# galaxydriveV3_5.net
KiCad netlist of a schematic drawn in EAGLE
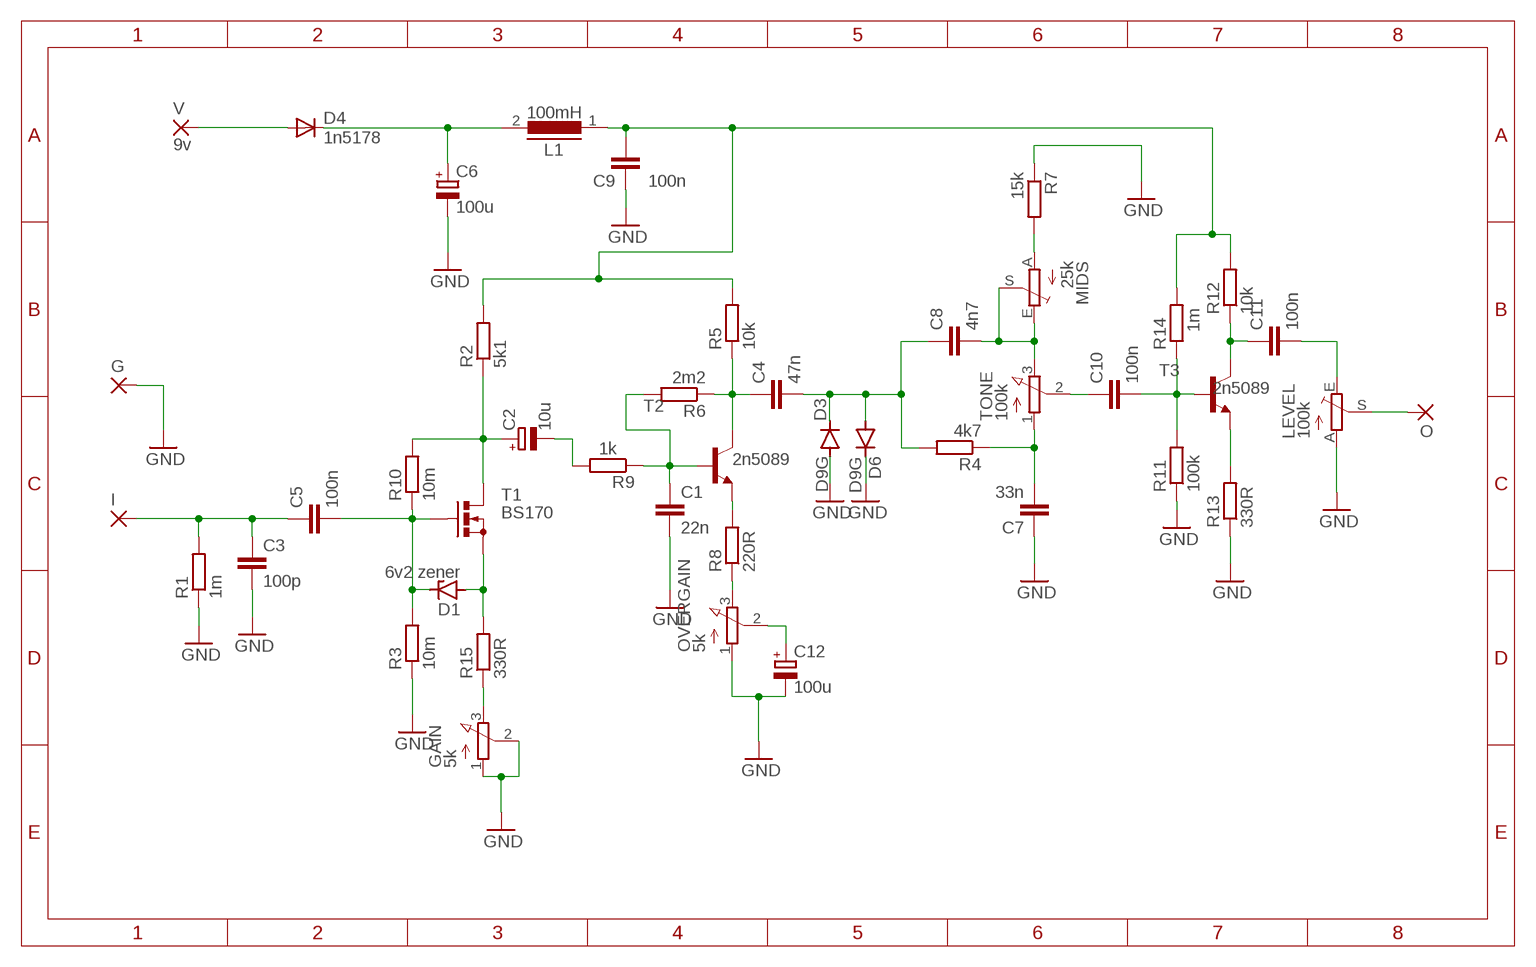
[diagram p0: schematic, sheet 1]

(export (version "E")
  (design (tool "Eeschema 10.0.6"))
  (components
    (comp (ref "C1")
      (value "22n")
      (footprint "eagle-import:C5B2.5")
      (libsource (lib "eagle-import") (part "C5/2.5"))
    )
    (comp (ref "C2")
      (value "10u")
      (footprint "eagle-import:E1,8-4")
      (libsource (lib "eagle-import") (part "CPOL-EUE1.8-4"))
    )
    (comp (ref "C3")
      (value "100p")
      (footprint "eagle-import:C5B2.5")
      (libsource (lib "eagle-import") (part "C5/2.5"))
    )
    (comp (ref "C4")
      (value "47n")
      (footprint "eagle-import:C5B2.5")
      (libsource (lib "eagle-import") (part "C5/2.5"))
    )
    (comp (ref "C5")
      (value "100n")
      (footprint "eagle-import:C5B2.5")
      (libsource (lib "eagle-import") (part "C5/2.5"))
    )
    (comp (ref "C6")
      (value "100u")
      (footprint "eagle-import:E2-4")
      (libsource (lib "eagle-import") (part "CPOL-EUE2-4"))
    )
    (comp (ref "C7")
      (value "33n")
      (footprint "eagle-import:C5B2.5")
      (libsource (lib "eagle-import") (part "C5/2.5"))
    )
    (comp (ref "C8")
      (value "4n7")
      (footprint "eagle-import:C5B2.5")
      (libsource (lib "eagle-import") (part "C5/2.5"))
    )
    (comp (ref "C9")
      (value "100n")
      (footprint "eagle-import:C5B2.5")
      (libsource (lib "eagle-import") (part "C5/2.5"))
    )
    (comp (ref "C10")
      (value "100n")
      (footprint "eagle-import:C5B2.5")
      (libsource (lib "eagle-import") (part "C5/2.5"))
    )
    (comp (ref "C11")
      (value "100n")
      (footprint "eagle-import:C5B2.5")
      (libsource (lib "eagle-import") (part "C5/2.5"))
    )
    (comp (ref "C12")
      (value "100u")
      (footprint "eagle-import:E2-4")
      (libsource (lib "eagle-import") (part "CPOL-EUE2-4"))
    )
    (comp (ref "D1")
      (value "6v2 zener")
      (footprint "eagle-import:DO34Z7")
      (libsource (lib "eagle-import") (part "BZX90"))
    )
    (comp (ref "D3")
      (value "D9G")
      (footprint "eagle-import:DO07")
      (libsource (lib "eagle-import") (part "OA91"))
    )
    (comp (ref "D4")
      (value "1n5178")
      (footprint "eagle-import:D-7.5")
      (libsource (lib "eagle-import") (part "DIODE-D-7.5"))
    )
    (comp (ref "D6")
      (value "D9G")
      (footprint "eagle-import:DO07")
      (libsource (lib "eagle-import") (part "OA91"))
    )
    (comp (ref "G")
      (value "2,15/1,0")
      (footprint "eagle-import:2,15_1,0")
      (libsource (lib "eagle-import") (part "2,15/1,0"))
    )
    (comp (ref "GAIN")
      (value "5k")
      (footprint "eagle-import:3RP_1610N")
      (libsource (lib "eagle-import") (part "HEXPOT1"))
    )
    (comp (ref "I")
      (value "2,15/1,0")
      (footprint "eagle-import:2,15_1,0")
      (libsource (lib "eagle-import") (part "2,15/1,0"))
    )
    (comp (ref "L1")
      (value "100mH")
      (footprint "eagle-import:MCC10")
      (libsource (lib "eagle-import") (part "MCC10"))
    )
    (comp (ref "LEVEL")
      (value "100k")
      (footprint "eagle-import:B25P")
      (libsource (lib "eagle-import") (part "TRIM_EU-B25P"))
    )
    (comp (ref "MIDS")
      (value "25k")
      (footprint "eagle-import:B25P")
      (libsource (lib "eagle-import") (part "TRIM_EU-B25P"))
    )
    (comp (ref "O")
      (value "2,15/1,0")
      (footprint "eagle-import:2,15_1,0")
      (libsource (lib "eagle-import") (part "2,15/1,0"))
    )
    (comp (ref "OVERGAIN")
      (value "5k")
      (footprint "eagle-import:3RP_1610N")
      (libsource (lib "eagle-import") (part "HEXPOT1"))
    )
    (comp (ref "R1")
      (value "1m")
      (footprint "eagle-import:0207_7")
      (libsource (lib "eagle-import") (part "R-EU_0207/7"))
    )
    (comp (ref "R2")
      (value "5k1")
      (footprint "eagle-import:0207_7")
      (libsource (lib "eagle-import") (part "R-EU_0207/7"))
    )
    (comp (ref "R3")
      (value "10m")
      (footprint "eagle-import:0207_7")
      (libsource (lib "eagle-import") (part "R-EU_0207/7"))
    )
    (comp (ref "R4")
      (value "4k7")
      (footprint "eagle-import:0207_7")
      (libsource (lib "eagle-import") (part "R-EU_0207/7"))
    )
    (comp (ref "R5")
      (value "10k")
      (footprint "eagle-import:0207_7")
      (libsource (lib "eagle-import") (part "R-EU_0207/7"))
    )
    (comp (ref "R6")
      (value "2m2")
      (footprint "eagle-import:0207_7")
      (libsource (lib "eagle-import") (part "R-EU_0207/7"))
    )
    (comp (ref "R7")
      (value "15k")
      (footprint "eagle-import:0207_7")
      (libsource (lib "eagle-import") (part "R-EU_0207/7"))
    )
    (comp (ref "R8")
      (value "220R")
      (footprint "eagle-import:0207_7")
      (libsource (lib "eagle-import") (part "R-EU_0207/7"))
    )
    (comp (ref "R9")
      (value "1k")
      (footprint "eagle-import:0207_7")
      (libsource (lib "eagle-import") (part "R-EU_0207/7"))
    )
    (comp (ref "R10")
      (value "10m")
      (footprint "eagle-import:0207_7")
      (libsource (lib "eagle-import") (part "R-EU_0207/7"))
    )
    (comp (ref "R11")
      (value "100k")
      (footprint "eagle-import:0207_7")
      (libsource (lib "eagle-import") (part "R-EU_0207/7"))
    )
    (comp (ref "R12")
      (value "10k")
      (footprint "eagle-import:0207_7")
      (libsource (lib "eagle-import") (part "R-EU_0207/7"))
    )
    (comp (ref "R13")
      (value "330R")
      (footprint "eagle-import:0207_7")
      (libsource (lib "eagle-import") (part "R-EU_0207/7"))
    )
    (comp (ref "R14")
      (value "1m")
      (footprint "eagle-import:0207_7")
      (libsource (lib "eagle-import") (part "R-EU_0207/7"))
    )
    (comp (ref "R15")
      (value "330R")
      (footprint "eagle-import:0207_7")
      (libsource (lib "eagle-import") (part "R-EU_0207/7"))
    )
    (comp (ref "T1")
      (value "BS170")
      (footprint "eagle-import:SOT54E")
      (libsource (lib "eagle-import") (part "BS170"))
    )
    (comp (ref "T2")
      (value "2n5089")
      (footprint "eagle-import:TO92")
      (libsource (lib "eagle-import") (part "2N3904"))
    )
    (comp (ref "T3")
      (value "2n5089")
      (footprint "eagle-import:TO92")
      (libsource (lib "eagle-import") (part "2N3904"))
    )
    (comp (ref "TONE")
      (value "100k")
      (footprint "eagle-import:3RP_1610N")
      (libsource (lib "eagle-import") (part "HEXPOT1"))
    )
    (comp (ref "V")
      (value "9v")
      (footprint "eagle-import:2,15_1,0")
      (libsource (lib "eagle-import") (part "2,15/1,0"))
    )
  )
  (nets
    (net (code "1") (name "GND") (class "Default")
      (node (ref "C1") (pin "2") (pinfunction "2_2") (pintype "passive"))
      (node (ref "C12") (pin "-") (pinfunction "-_-") (pintype "passive"))
      (node (ref "C3") (pin "2") (pinfunction "2_2") (pintype "passive"))
      (node (ref "C6") (pin "-") (pinfunction "-_-") (pintype "passive"))
      (node (ref "C7") (pin "1") (pinfunction "1_1") (pintype "passive"))
      (node (ref "C9") (pin "1") (pinfunction "1_1") (pintype "passive"))
      (node (ref "D3") (pin "A") (pinfunction "A_A") (pintype "passive"))
      (node (ref "D6") (pin "C") (pinfunction "C_C") (pintype "passive"))
      (node (ref "G") (pin "1") (pinfunction "P_1") (pintype "passive"))
      (node (ref "GAIN") (pin "1") (pinfunction "A_1") (pintype "passive"))
      (node (ref "GAIN") (pin "2") (pinfunction "S_2") (pintype "passive"))
      (node (ref "LEVEL") (pin "A") (pinfunction "A_A") (pintype "passive"))
      (node (ref "OVERGAIN") (pin "1") (pinfunction "A_1") (pintype "passive"))
      (node (ref "R1") (pin "1") (pinfunction "1_1") (pintype "passive"))
      (node (ref "R11") (pin "1") (pinfunction "1_1") (pintype "passive"))
      (node (ref "R13") (pin "1") (pinfunction "1_1") (pintype "passive"))
      (node (ref "R3") (pin "1") (pinfunction "1_1") (pintype "passive"))
      (node (ref "R7") (pin "1") (pinfunction "1_1") (pintype "passive"))
    )
    (net (code "2") (name "Net-(C2-Pad+)") (class "Default")
      (node (ref "C2") (pin "+") (pinfunction "+_+") (pintype "passive"))
      (node (ref "R10") (pin "2") (pinfunction "2_2") (pintype "passive"))
      (node (ref "R2") (pin "1") (pinfunction "1_1") (pintype "passive"))
      (node (ref "T1") (pin "D") (pinfunction "D_D") (pintype "passive"))
    )
    (net (code "3") (name "Net-(C2-Pad-)") (class "Default")
      (node (ref "C2") (pin "-") (pinfunction "-_-") (pintype "passive"))
      (node (ref "R9") (pin "2") (pinfunction "2_2") (pintype "passive"))
    )
    (net (code "4") (name "Net-(C4-Pad2)") (class "Default")
      (node (ref "C4") (pin "2") (pinfunction "2_2") (pintype "passive"))
      (node (ref "C8") (pin "1") (pinfunction "1_1") (pintype "passive"))
      (node (ref "D3") (pin "C") (pinfunction "C_C") (pintype "passive"))
      (node (ref "D6") (pin "A") (pinfunction "A_A") (pintype "passive"))
      (node (ref "R4") (pin "2") (pinfunction "2_2") (pintype "passive"))
    )
    (net (code "5") (name "Net-(C5-Pad2)") (class "Default")
      (node (ref "C5") (pin "2") (pinfunction "2_2") (pintype "passive"))
      (node (ref "D1") (pin "C") (pinfunction "C_C") (pintype "passive"))
      (node (ref "R10") (pin "1") (pinfunction "1_1") (pintype "passive"))
      (node (ref "R3") (pin "2") (pinfunction "2_2") (pintype "passive"))
      (node (ref "T1") (pin "G") (pinfunction "G_G") (pintype "passive"))
    )
    (net (code "6") (name "Net-(C6-Pad+)") (class "Default")
      (node (ref "C6") (pin "+") (pinfunction "+_+") (pintype "passive"))
      (node (ref "D4") (pin "C") (pinfunction "C_C") (pintype "passive"))
      (node (ref "L1") (pin "2") (pinfunction "2_2") (pintype "passive"))
    )
    (net (code "7") (name "Net-(C9-Pad2)") (class "Default")
      (node (ref "C9") (pin "2") (pinfunction "2_2") (pintype "passive"))
      (node (ref "L1") (pin "1") (pinfunction "1_1") (pintype "passive"))
      (node (ref "R12") (pin "2") (pinfunction "2_2") (pintype "passive"))
      (node (ref "R14") (pin "2") (pinfunction "2_2") (pintype "passive"))
      (node (ref "R2") (pin "2") (pinfunction "2_2") (pintype "passive"))
      (node (ref "R5") (pin "2") (pinfunction "2_2") (pintype "passive"))
    )
    (net (code "8") (name "Net-(C11-Pad2)") (class "Default")
      (node (ref "C11") (pin "2") (pinfunction "2_2") (pintype "passive"))
      (node (ref "LEVEL") (pin "E") (pinfunction "E_E") (pintype "passive"))
    )
    (net (code "9") (name "Net-(D1-PadA)") (class "Default")
      (node (ref "D1") (pin "A") (pinfunction "A_A") (pintype "passive"))
      (node (ref "R15") (pin "2") (pinfunction "2_2") (pintype "passive"))
      (node (ref "T1") (pin "S") (pinfunction "S_S") (pintype "passive"))
    )
    (net (code "10") (name "Net-(GAIN-E)") (class "Default")
      (node (ref "GAIN") (pin "3") (pinfunction "E_3") (pintype "passive"))
      (node (ref "R15") (pin "1") (pinfunction "1_1") (pintype "passive"))
    )
    (net (code "11") (name "Net-(I-P)") (class "Default")
      (node (ref "C3") (pin "1") (pinfunction "1_1") (pintype "passive"))
      (node (ref "C5") (pin "1") (pinfunction "1_1") (pintype "passive"))
      (node (ref "I") (pin "1") (pinfunction "P_1") (pintype "passive"))
      (node (ref "R1") (pin "2") (pinfunction "2_2") (pintype "passive"))
    )
    (net (code "12") (name "Net-(MIDS-PadA)") (class "Default")
      (node (ref "MIDS") (pin "A") (pinfunction "A_A") (pintype "passive"))
      (node (ref "R7") (pin "2") (pinfunction "2_2") (pintype "passive"))
    )
    (net (code "13") (name "Net-(O-P)") (class "Default")
      (node (ref "LEVEL") (pin "S") (pinfunction "S_S") (pintype "passive"))
      (node (ref "O") (pin "1") (pinfunction "P_1") (pintype "passive"))
    )
    (net (code "14") (name "Net-(OVERGAIN-E)") (class "Default")
      (node (ref "OVERGAIN") (pin "3") (pinfunction "E_3") (pintype "passive"))
      (node (ref "R8") (pin "1") (pinfunction "1_1") (pintype "passive"))
    )
    (net (code "15") (name "Net-(OVERGAIN-S)") (class "Default")
      (node (ref "C12") (pin "+") (pinfunction "+_+") (pintype "passive"))
      (node (ref "OVERGAIN") (pin "2") (pinfunction "S_2") (pintype "passive"))
    )
    (net (code "16") (name "Net-(T2-B)") (class "Default")
      (node (ref "C1") (pin "1") (pinfunction "1_1") (pintype "passive"))
      (node (ref "R6") (pin "2") (pinfunction "2_2") (pintype "passive"))
      (node (ref "R9") (pin "1") (pinfunction "1_1") (pintype "passive"))
      (node (ref "T2") (pin "2") (pinfunction "B_2") (pintype "passive"))
    )
    (net (code "17") (name "Net-(T2-C)") (class "Default")
      (node (ref "C4") (pin "1") (pinfunction "1_1") (pintype "passive"))
      (node (ref "R5") (pin "1") (pinfunction "1_1") (pintype "passive"))
      (node (ref "R6") (pin "1") (pinfunction "1_1") (pintype "passive"))
      (node (ref "T2") (pin "1") (pinfunction "C_1") (pintype "passive"))
    )
    (net (code "18") (name "Net-(T2-E)") (class "Default")
      (node (ref "R8") (pin "2") (pinfunction "2_2") (pintype "passive"))
      (node (ref "T2") (pin "3") (pinfunction "E_3") (pintype "passive"))
    )
    (net (code "19") (name "Net-(T3-B)") (class "Default")
      (node (ref "C10") (pin "2") (pinfunction "2_2") (pintype "passive"))
      (node (ref "R11") (pin "2") (pinfunction "2_2") (pintype "passive"))
      (node (ref "R14") (pin "1") (pinfunction "1_1") (pintype "passive"))
      (node (ref "T3") (pin "2") (pinfunction "B_2") (pintype "passive"))
    )
    (net (code "20") (name "Net-(T3-C)") (class "Default")
      (node (ref "C11") (pin "1") (pinfunction "1_1") (pintype "passive"))
      (node (ref "R12") (pin "1") (pinfunction "1_1") (pintype "passive"))
      (node (ref "T3") (pin "1") (pinfunction "C_1") (pintype "passive"))
    )
    (net (code "21") (name "Net-(T3-E)") (class "Default")
      (node (ref "R13") (pin "2") (pinfunction "2_2") (pintype "passive"))
      (node (ref "T3") (pin "3") (pinfunction "E_3") (pintype "passive"))
    )
    (net (code "22") (name "Net-(TONE-A)") (class "Default")
      (node (ref "C7") (pin "2") (pinfunction "2_2") (pintype "passive"))
      (node (ref "R4") (pin "1") (pinfunction "1_1") (pintype "passive"))
      (node (ref "TONE") (pin "1") (pinfunction "A_1") (pintype "passive"))
    )
    (net (code "23") (name "Net-(TONE-E)") (class "Default")
      (node (ref "C8") (pin "2") (pinfunction "2_2") (pintype "passive"))
      (node (ref "MIDS") (pin "E") (pinfunction "E_E") (pintype "passive"))
      (node (ref "MIDS") (pin "S") (pinfunction "S_S") (pintype "passive"))
      (node (ref "TONE") (pin "3") (pinfunction "E_3") (pintype "passive"))
    )
    (net (code "24") (name "Net-(TONE-S)") (class "Default")
      (node (ref "C10") (pin "1") (pinfunction "1_1") (pintype "passive"))
      (node (ref "TONE") (pin "2") (pinfunction "S_2") (pintype "passive"))
    )
    (net (code "25") (name "Net-(V-P)") (class "Default")
      (node (ref "D4") (pin "A") (pinfunction "A_A") (pintype "passive"))
      (node (ref "V") (pin "1") (pinfunction "P_1") (pintype "passive"))
    )
  )
)
